# PCM2706_Bus_Powered_USB_DAC_4.net
KiCad netlist of a schematic drawn in Altium Designer
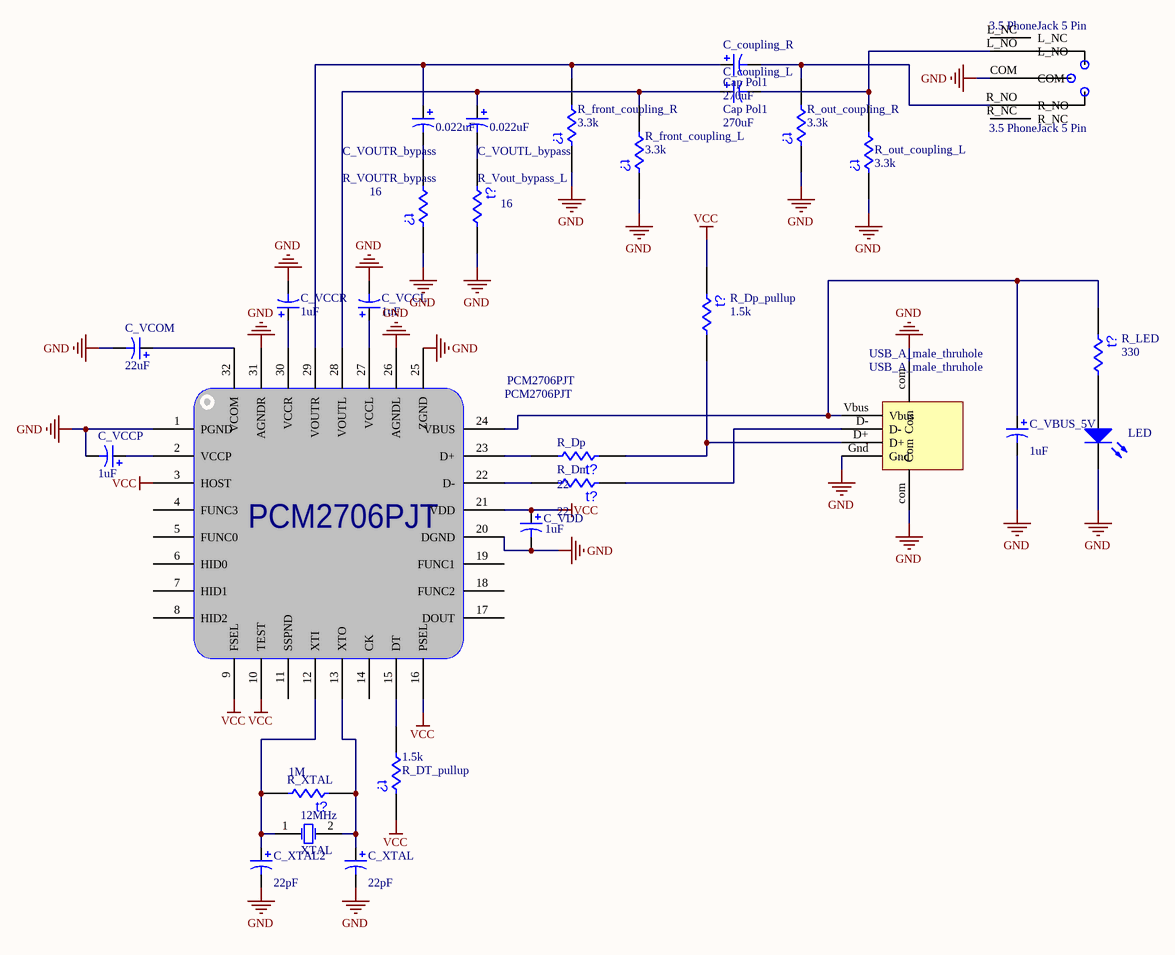
[diagram p0: PCM2706 Bus Powered USB DAC 4.SchDoc]

(export (version "E")
  (design (tool "Eeschema 10.0.6"))
  (components
    (comp (ref "1.5k")
      (value "R_DT_pullup")
      (footprint "6-0805_N")
      (description "Thermistor")
      (fields (field (name "PUBLISHER") "Altium Limited"))
      (libsource (lib "Miscellaneous Devices") (part "Res Thermal"))
    )
    (comp (ref "3.5 PhoneJack 5 Pin")
      (value "3.5 PhoneJack 5 Pin")
      (footprint "3.5 PhoneJack 5 Pin")
      (libsource (lib "misc") (part "3.5 PhoneJack 5 Pin"))
    )
    (comp (ref "12MHz")
      (value "XTAL")
      (footprint "12MHz Crystal OSC through hole")
      (description "Crystal Oscillator")
      (fields (field (name "PUBLISHER") "Altium Limited"))
      (libsource (lib "Miscellaneous Devices") (part "XTAL"))
    )
    (comp (ref "C_coupling_L")
      (value "Cap Pol1")
      (footprint "CAP_270uf_16V_solid_Aluminum")
      (description "Polarized Capacitor (Radial)")
      (fields (field (name "ALTIUM_VALUE") "270uF") (field (name "PUBLISHER") "Altium Limited"))
      (libsource (lib "Miscellaneous Devices") (part "Cap Pol1"))
    )
    (comp (ref "C_coupling_R")
      (value "Cap Pol1")
      (footprint "CAP_270uf_16V_solid_Aluminum")
      (description "Polarized Capacitor (Radial)")
      (fields (field (name "ALTIUM_VALUE") "270uF") (field (name "PUBLISHER") "Altium Limited"))
      (libsource (lib "Miscellaneous Devices") (part "Cap Pol1"))
    )
    (comp (ref "C_VBUS_5V")
      (value "1uF")
      (footprint "C0805")
      (description "Polarized Capacitor (Surface Mount)")
      (fields (field (name "PUBLISHER") "Altium Limited"))
      (libsource (lib "Miscellaneous Devices") (part "Cap Pol3"))
    )
    (comp (ref "C_VCCL")
      (value "1uF")
      (footprint "C0805")
      (description "Polarized Capacitor (Surface Mount)")
      (fields (field (name "PUBLISHER") "Altium Limited"))
      (libsource (lib "Miscellaneous Devices") (part "Cap Pol3"))
    )
    (comp (ref "C_VCCP")
      (value "1uF")
      (footprint "C0805")
      (description "Polarized Capacitor (Surface Mount)")
      (fields (field (name "PUBLISHER") "Altium Limited"))
      (libsource (lib "Miscellaneous Devices") (part "Cap Pol3"))
    )
    (comp (ref "C_VCCR")
      (value "1uF")
      (footprint "C0805")
      (description "Polarized Capacitor (Surface Mount)")
      (fields (field (name "PUBLISHER") "Altium Limited"))
      (libsource (lib "Miscellaneous Devices") (part "Cap Pol3"))
    )
    (comp (ref "C_VCOM")
      (value "22uF")
      (footprint "CAPC3216N")
      (description "Polarized Capacitor (Surface Mount)")
      (fields (field (name "PUBLISHER") "Altium Limited"))
      (libsource (lib "Miscellaneous Devices") (part "Cap Pol3"))
    )
    (comp (ref "C_VDD")
      (value "1uF")
      (footprint "C0805")
      (description "Polarized Capacitor (Surface Mount)")
      (fields (field (name "PUBLISHER") "Altium Limited"))
      (libsource (lib "Miscellaneous Devices") (part "Cap Pol3"))
    )
    (comp (ref "C_VOUTL_bypass")
      (value "0.022uF")
      (footprint "C0805")
      (description "Polarized Capacitor (Surface Mount)")
      (fields (field (name "PUBLISHER") "Altium Limited"))
      (libsource (lib "Miscellaneous Devices") (part "Cap Pol3"))
    )
    (comp (ref "C_VOUTR_bypass")
      (value "0.022uF")
      (footprint "C0805")
      (description "Polarized Capacitor (Surface Mount)")
      (fields (field (name "PUBLISHER") "Altium Limited"))
      (libsource (lib "Miscellaneous Devices") (part "Cap Pol3"))
    )
    (comp (ref "C_XTAL")
      (value "22pF")
      (footprint "C0805")
      (description "Polarized Capacitor (Surface Mount)")
      (fields (field (name "PUBLISHER") "Altium Limited"))
      (libsource (lib "Miscellaneous Devices") (part "Cap Pol3"))
    )
    (comp (ref "C_XTAL2")
      (value "22pF")
      (footprint "C0805")
      (description "Polarized Capacitor (Surface Mount)")
      (fields (field (name "PUBLISHER") "Altium Limited"))
      (libsource (lib "Miscellaneous Devices") (part "Cap Pol3"))
    )
    (comp (ref "LED")
      (value "~")
      (footprint "CAPC1608N")
      (description "Typical RED, GREEN, YELLOW, AMBER GaAs LED")
      (fields (field (name "PUBLISHER") "Altium Limited"))
      (libsource (lib "Miscellaneous Devices") (part "LED2"))
    )
    (comp (ref "PCM2706PJT")
      (value "PCM2706PJT")
      (footprint "S-PQFP-N32-2mm-out")
      (libsource (lib "misc") (part "PCM2706PJT"))
    )
    (comp (ref "R_Dm")
      (value "22")
      (footprint "6-0805_N")
      (description "Thermistor")
      (fields (field (name "PUBLISHER") "Altium Limited"))
      (libsource (lib "Miscellaneous Devices") (part "Res Thermal"))
    )
    (comp (ref "R_Dp")
      (value "22")
      (footprint "6-0805_N")
      (description "Thermistor")
      (fields (field (name "PUBLISHER") "Altium Limited"))
      (libsource (lib "Miscellaneous Devices") (part "Res Thermal"))
    )
    (comp (ref "R_Dp_pullup")
      (value "1.5k")
      (footprint "6-0805_N")
      (description "Thermistor")
      (fields (field (name "PUBLISHER") "Altium Limited"))
      (libsource (lib "Miscellaneous Devices") (part "Res Thermal"))
    )
    (comp (ref "R_front_coupling_L")
      (value "3.3k")
      (footprint "6-0805_N")
      (description "Thermistor")
      (fields (field (name "PUBLISHER") "Altium Limited"))
      (libsource (lib "Miscellaneous Devices") (part "Res Thermal"))
    )
    (comp (ref "R_front_coupling_R")
      (value "3.3k")
      (footprint "6-0805_N")
      (description "Thermistor")
      (fields (field (name "PUBLISHER") "Altium Limited"))
      (libsource (lib "Miscellaneous Devices") (part "Res Thermal"))
    )
    (comp (ref "R_LED")
      (value "330")
      (footprint "6-0805_N")
      (description "Thermistor")
      (fields (field (name "PUBLISHER") "Altium Limited"))
      (libsource (lib "Miscellaneous Devices") (part "Res Thermal"))
    )
    (comp (ref "R_out_coupling_L")
      (value "3.3k")
      (footprint "6-0805_N")
      (description "Thermistor")
      (fields (field (name "PUBLISHER") "Altium Limited"))
      (libsource (lib "Miscellaneous Devices") (part "Res Thermal"))
    )
    (comp (ref "R_out_coupling_R")
      (value "3.3k")
      (footprint "6-0805_N")
      (description "Thermistor")
      (fields (field (name "PUBLISHER") "Altium Limited"))
      (libsource (lib "Miscellaneous Devices") (part "Res Thermal"))
    )
    (comp (ref "R_VOUTR_bypass")
      (value "16")
      (footprint "6-0805_N")
      (description "Thermistor")
      (fields (field (name "PUBLISHER") "Altium Limited"))
      (libsource (lib "Miscellaneous Devices") (part "Res Thermal"))
    )
    (comp (ref "R_Vout_bypass_L")
      (value "16")
      (footprint "6-0805_N")
      (description "Thermistor")
      (fields (field (name "PUBLISHER") "Altium Limited"))
      (libsource (lib "Miscellaneous Devices") (part "Res Thermal"))
    )
    (comp (ref "R_XTAL")
      (value "1M")
      (footprint "6-0805_N")
      (description "Thermistor")
      (fields (field (name "PUBLISHER") "Altium Limited"))
      (libsource (lib "Miscellaneous Devices") (part "Res Thermal"))
    )
    (comp (ref "USB_A_male_thruhole")
      (value "USB_A_male_thruhole")
      (footprint "USB_A_male_thruhole")
      (libsource (lib "misc") (part "USB_A_male_thruhole"))
    )
  )
  (nets
    (net (code "1") (name "GND") (class "Default")
      (node (ref "3.5 PhoneJack 5 Pin") (pin "COM") (pinfunction "COM_COM") (pintype "passive"))
      (node (ref "C_VBUS_5V") (pin "2") (pinfunction "2_2") (pintype "passive"))
      (node (ref "C_VCCL") (pin "2") (pinfunction "2_2") (pintype "passive"))
      (node (ref "C_VCCP") (pin "2") (pinfunction "2_2") (pintype "passive"))
      (node (ref "C_VCCR") (pin "2") (pinfunction "2_2") (pintype "passive"))
      (node (ref "C_VCOM") (pin "2") (pinfunction "2_2") (pintype "passive"))
      (node (ref "C_VDD") (pin "2") (pinfunction "2_2") (pintype "passive"))
      (node (ref "C_XTAL") (pin "2") (pinfunction "2_2") (pintype "passive"))
      (node (ref "C_XTAL2") (pin "2") (pinfunction "2_2") (pintype "passive"))
      (node (ref "LED") (pin "2") (pinfunction "K_2") (pintype "passive"))
      (node (ref "PCM2706PJT") (pin "1") (pinfunction "PGND_1") (pintype "passive"))
      (node (ref "PCM2706PJT") (pin "20") (pinfunction "DGND_20") (pintype "passive"))
      (node (ref "PCM2706PJT") (pin "25") (pinfunction "ZGND_25") (pintype "passive"))
      (node (ref "PCM2706PJT") (pin "26") (pinfunction "AGNDL_26") (pintype "passive"))
      (node (ref "PCM2706PJT") (pin "31") (pinfunction "AGNDR_31") (pintype "passive"))
      (node (ref "R_VOUTR_bypass") (pin "1") (pinfunction "1_1") (pintype "passive"))
      (node (ref "R_Vout_bypass_L") (pin "2") (pinfunction "2_2") (pintype "passive"))
      (node (ref "R_front_coupling_L") (pin "1") (pinfunction "1_1") (pintype "passive"))
      (node (ref "R_front_coupling_R") (pin "1") (pinfunction "1_1") (pintype "passive"))
      (node (ref "R_out_coupling_L") (pin "1") (pinfunction "1_1") (pintype "passive"))
      (node (ref "R_out_coupling_R") (pin "1") (pinfunction "1_1") (pintype "passive"))
      (node (ref "USB_A_male_thruhole") (pin "Gnd") (pinfunction "Gnd_Gnd") (pintype "passive"))
      (node (ref "USB_A_male_thruhole") (pin "com") (pinfunction "Com_com") (pintype "passive"))
    )
    (net (code "2") (name "Net-(3.5 PhoneJack 5 Pin-PadL_NO)") (class "Default")
      (node (ref "3.5 PhoneJack 5 Pin") (pin "L_NO") (pinfunction "L_NO_L_NO") (pintype "passive"))
      (node (ref "C_coupling_L") (pin "2") (pinfunction "2_2") (pintype "passive"))
      (node (ref "R_out_coupling_L") (pin "2") (pinfunction "2_2") (pintype "passive"))
    )
    (net (code "3") (name "Net-(3.5 PhoneJack 5 Pin-PadR_NO)") (class "Default")
      (node (ref "3.5 PhoneJack 5 Pin") (pin "R_NO") (pinfunction "R_NO_R_NO") (pintype "passive"))
      (node (ref "C_coupling_R") (pin "2") (pinfunction "2_2") (pintype "passive"))
      (node (ref "R_out_coupling_R") (pin "2") (pinfunction "2_2") (pintype "passive"))
    )
    (net (code "4") (name "Net-(12MHz-OSC1)") (class "Default")
      (node (ref "12MHz") (pin "1") (pinfunction "OSC1_1") (pintype "passive"))
      (node (ref "C_XTAL2") (pin "1") (pinfunction "1_1") (pintype "passive"))
      (node (ref "PCM2706PJT") (pin "12") (pinfunction "XTI_12") (pintype "passive"))
      (node (ref "R_XTAL") (pin "2") (pinfunction "2_2") (pintype "passive"))
    )
    (net (code "5") (name "Net-(12MHz-OSC2)") (class "Default")
      (node (ref "12MHz") (pin "2") (pinfunction "OSC2_2") (pintype "passive"))
      (node (ref "C_XTAL") (pin "1") (pinfunction "1_1") (pintype "passive"))
      (node (ref "PCM2706PJT") (pin "13") (pinfunction "XTO_13") (pintype "passive"))
      (node (ref "R_XTAL") (pin "1") (pinfunction "1_1") (pintype "passive"))
    )
    (net (code "6") (name "Net-(C_VOUTL_bypass-Pad2)") (class "Default")
      (node (ref "C_VOUTL_bypass") (pin "2") (pinfunction "2_2") (pintype "passive"))
      (node (ref "R_Vout_bypass_L") (pin "1") (pinfunction "1_1") (pintype "passive"))
    )
    (net (code "7") (name "Net-(C_VOUTR_bypass-Pad2)") (class "Default")
      (node (ref "C_VOUTR_bypass") (pin "2") (pinfunction "2_2") (pintype "passive"))
      (node (ref "R_VOUTR_bypass") (pin "2") (pinfunction "2_2") (pintype "passive"))
    )
    (net (code "8") (name "Net-(LED-A)") (class "Default")
      (node (ref "LED") (pin "1") (pinfunction "A_1") (pintype "passive"))
      (node (ref "R_LED") (pin "2") (pinfunction "2_2") (pintype "passive"))
    )
    (net (code "9") (name "Net-(PCM2706PJT-D+)") (class "Default")
      (node (ref "PCM2706PJT") (pin "23") (pinfunction "D+_23") (pintype "passive"))
      (node (ref "R_Dp") (pin "2") (pinfunction "2_2") (pintype "passive"))
    )
    (net (code "10") (name "Net-(PCM2706PJT-D-)") (class "Default")
      (node (ref "PCM2706PJT") (pin "22") (pinfunction "D-_22") (pintype "passive"))
      (node (ref "R_Dm") (pin "2") (pinfunction "2_2") (pintype "passive"))
    )
    (net (code "11") (name "Net-(PCM2706PJT-DT)") (class "Default")
      (node (ref "1.5k") (pin "2") (pinfunction "2_2") (pintype "passive"))
      (node (ref "PCM2706PJT") (pin "15") (pinfunction "DT_15") (pintype "passive"))
    )
    (net (code "12") (name "Net-(PCM2706PJT-VBUS)") (class "Default")
      (node (ref "C_VBUS_5V") (pin "1") (pinfunction "1_1") (pintype "passive"))
      (node (ref "PCM2706PJT") (pin "24") (pinfunction "VBUS_24") (pintype "passive"))
      (node (ref "R_LED") (pin "1") (pinfunction "1_1") (pintype "passive"))
      (node (ref "USB_A_male_thruhole") (pin "Vbus") (pinfunction "Vbus_Vbus") (pintype "passive"))
    )
    (net (code "13") (name "Net-(PCM2706PJT-VCCL)") (class "Default")
      (node (ref "C_VCCL") (pin "1") (pinfunction "1_1") (pintype "passive"))
      (node (ref "PCM2706PJT") (pin "27") (pinfunction "VCCL_27") (pintype "passive"))
    )
    (net (code "14") (name "Net-(PCM2706PJT-VCCP)") (class "Default")
      (node (ref "C_VCCP") (pin "1") (pinfunction "1_1") (pintype "passive"))
      (node (ref "PCM2706PJT") (pin "2") (pinfunction "VCCP_2") (pintype "passive"))
    )
    (net (code "15") (name "Net-(PCM2706PJT-VCCR)") (class "Default")
      (node (ref "C_VCCR") (pin "1") (pinfunction "1_1") (pintype "passive"))
      (node (ref "PCM2706PJT") (pin "30") (pinfunction "VCCR_30") (pintype "passive"))
    )
    (net (code "16") (name "Net-(PCM2706PJT-VCOM)") (class "Default")
      (node (ref "C_VCOM") (pin "1") (pinfunction "1_1") (pintype "passive"))
      (node (ref "PCM2706PJT") (pin "32") (pinfunction "VCOM_32") (pintype "passive"))
    )
    (net (code "17") (name "Net-(PCM2706PJT-VOUTL)") (class "Default")
      (node (ref "C_VOUTL_bypass") (pin "1") (pinfunction "1_1") (pintype "passive"))
      (node (ref "C_coupling_L") (pin "1") (pinfunction "1_1") (pintype "passive"))
      (node (ref "PCM2706PJT") (pin "28") (pinfunction "VOUTL_28") (pintype "passive"))
      (node (ref "R_front_coupling_L") (pin "2") (pinfunction "2_2") (pintype "passive"))
    )
    (net (code "18") (name "Net-(PCM2706PJT-VOUTR)") (class "Default")
      (node (ref "C_VOUTR_bypass") (pin "1") (pinfunction "1_1") (pintype "passive"))
      (node (ref "C_coupling_R") (pin "1") (pinfunction "1_1") (pintype "passive"))
      (node (ref "PCM2706PJT") (pin "29") (pinfunction "VOUTR_29") (pintype "passive"))
      (node (ref "R_front_coupling_R") (pin "2") (pinfunction "2_2") (pintype "passive"))
    )
    (net (code "19") (name "Net-(R_Dm-Pad1)") (class "Default")
      (node (ref "R_Dm") (pin "1") (pinfunction "1_1") (pintype "passive"))
      (node (ref "USB_A_male_thruhole") (pin "D-") (pinfunction "D-_D-") (pintype "passive"))
    )
    (net (code "20") (name "Net-(R_Dp-Pad1)") (class "Default")
      (node (ref "R_Dp") (pin "1") (pinfunction "1_1") (pintype "passive"))
      (node (ref "R_Dp_pullup") (pin "2") (pinfunction "2_2") (pintype "passive"))
      (node (ref "USB_A_male_thruhole") (pin "D+") (pinfunction "D+_D+") (pintype "passive"))
    )
    (net (code "21") (name "VCC") (class "Default")
      (node (ref "1.5k") (pin "1") (pinfunction "1_1") (pintype "passive"))
      (node (ref "C_VDD") (pin "1") (pinfunction "1_1") (pintype "passive"))
      (node (ref "PCM2706PJT") (pin "10") (pinfunction "TEST_10") (pintype "passive"))
      (node (ref "PCM2706PJT") (pin "16") (pinfunction "PSEL_16") (pintype "passive"))
      (node (ref "PCM2706PJT") (pin "21") (pinfunction "VDD_21") (pintype "passive"))
      (node (ref "PCM2706PJT") (pin "3") (pinfunction "HOST_3") (pintype "passive"))
      (node (ref "PCM2706PJT") (pin "9") (pinfunction "FSEL_9") (pintype "passive"))
      (node (ref "R_Dp_pullup") (pin "1") (pinfunction "1_1") (pintype "passive"))
    )
    (net (code "22") (name "unconnected-(3.5 PhoneJack 5 Pin-PadL_NC)") (class "Default")
      (node (ref "3.5 PhoneJack 5 Pin") (pin "L_NC") (pinfunction "L_NC_L_NC") (pintype "passive"))
    )
    (net (code "23") (name "unconnected-(3.5 PhoneJack 5 Pin-PadR_NC)") (class "Default")
      (node (ref "3.5 PhoneJack 5 Pin") (pin "R_NC") (pinfunction "R_NC_R_NC") (pintype "passive"))
    )
    (net (code "24") (name "unconnected-(PCM2706PJT-CK-Pad14)") (class "Default")
      (node (ref "PCM2706PJT") (pin "14") (pinfunction "CK_14") (pintype "passive"))
    )
    (net (code "25") (name "unconnected-(PCM2706PJT-DOUT-Pad17)") (class "Default")
      (node (ref "PCM2706PJT") (pin "17") (pinfunction "DOUT_17") (pintype "passive"))
    )
    (net (code "26") (name "unconnected-(PCM2706PJT-FUNC0-Pad5)") (class "Default")
      (node (ref "PCM2706PJT") (pin "5") (pinfunction "FUNC0_5") (pintype "passive"))
    )
    (net (code "27") (name "unconnected-(PCM2706PJT-FUNC1-Pad19)") (class "Default")
      (node (ref "PCM2706PJT") (pin "19") (pinfunction "FUNC1_19") (pintype "passive"))
    )
    (net (code "28") (name "unconnected-(PCM2706PJT-FUNC2-Pad18)") (class "Default")
      (node (ref "PCM2706PJT") (pin "18") (pinfunction "FUNC2_18") (pintype "passive"))
    )
    (net (code "29") (name "unconnected-(PCM2706PJT-FUNC3-Pad4)") (class "Default")
      (node (ref "PCM2706PJT") (pin "4") (pinfunction "FUNC3_4") (pintype "passive"))
    )
    (net (code "30") (name "unconnected-(PCM2706PJT-HID0-Pad6)") (class "Default")
      (node (ref "PCM2706PJT") (pin "6") (pinfunction "HID0_6") (pintype "passive"))
    )
    (net (code "31") (name "unconnected-(PCM2706PJT-HID1-Pad7)") (class "Default")
      (node (ref "PCM2706PJT") (pin "7") (pinfunction "HID1_7") (pintype "passive"))
    )
    (net (code "32") (name "unconnected-(PCM2706PJT-HID2-Pad8)") (class "Default")
      (node (ref "PCM2706PJT") (pin "8") (pinfunction "HID2_8") (pintype "passive"))
    )
    (net (code "33") (name "unconnected-(PCM2706PJT-SSPND-Pad11)") (class "Default")
      (node (ref "PCM2706PJT") (pin "11") (pinfunction "SSPND_11") (pintype "passive"))
    )
  )
)
